# One_Dimensional_Pong_-_Rev_A_1.net
KiCad netlist of a schematic drawn in EAGLE
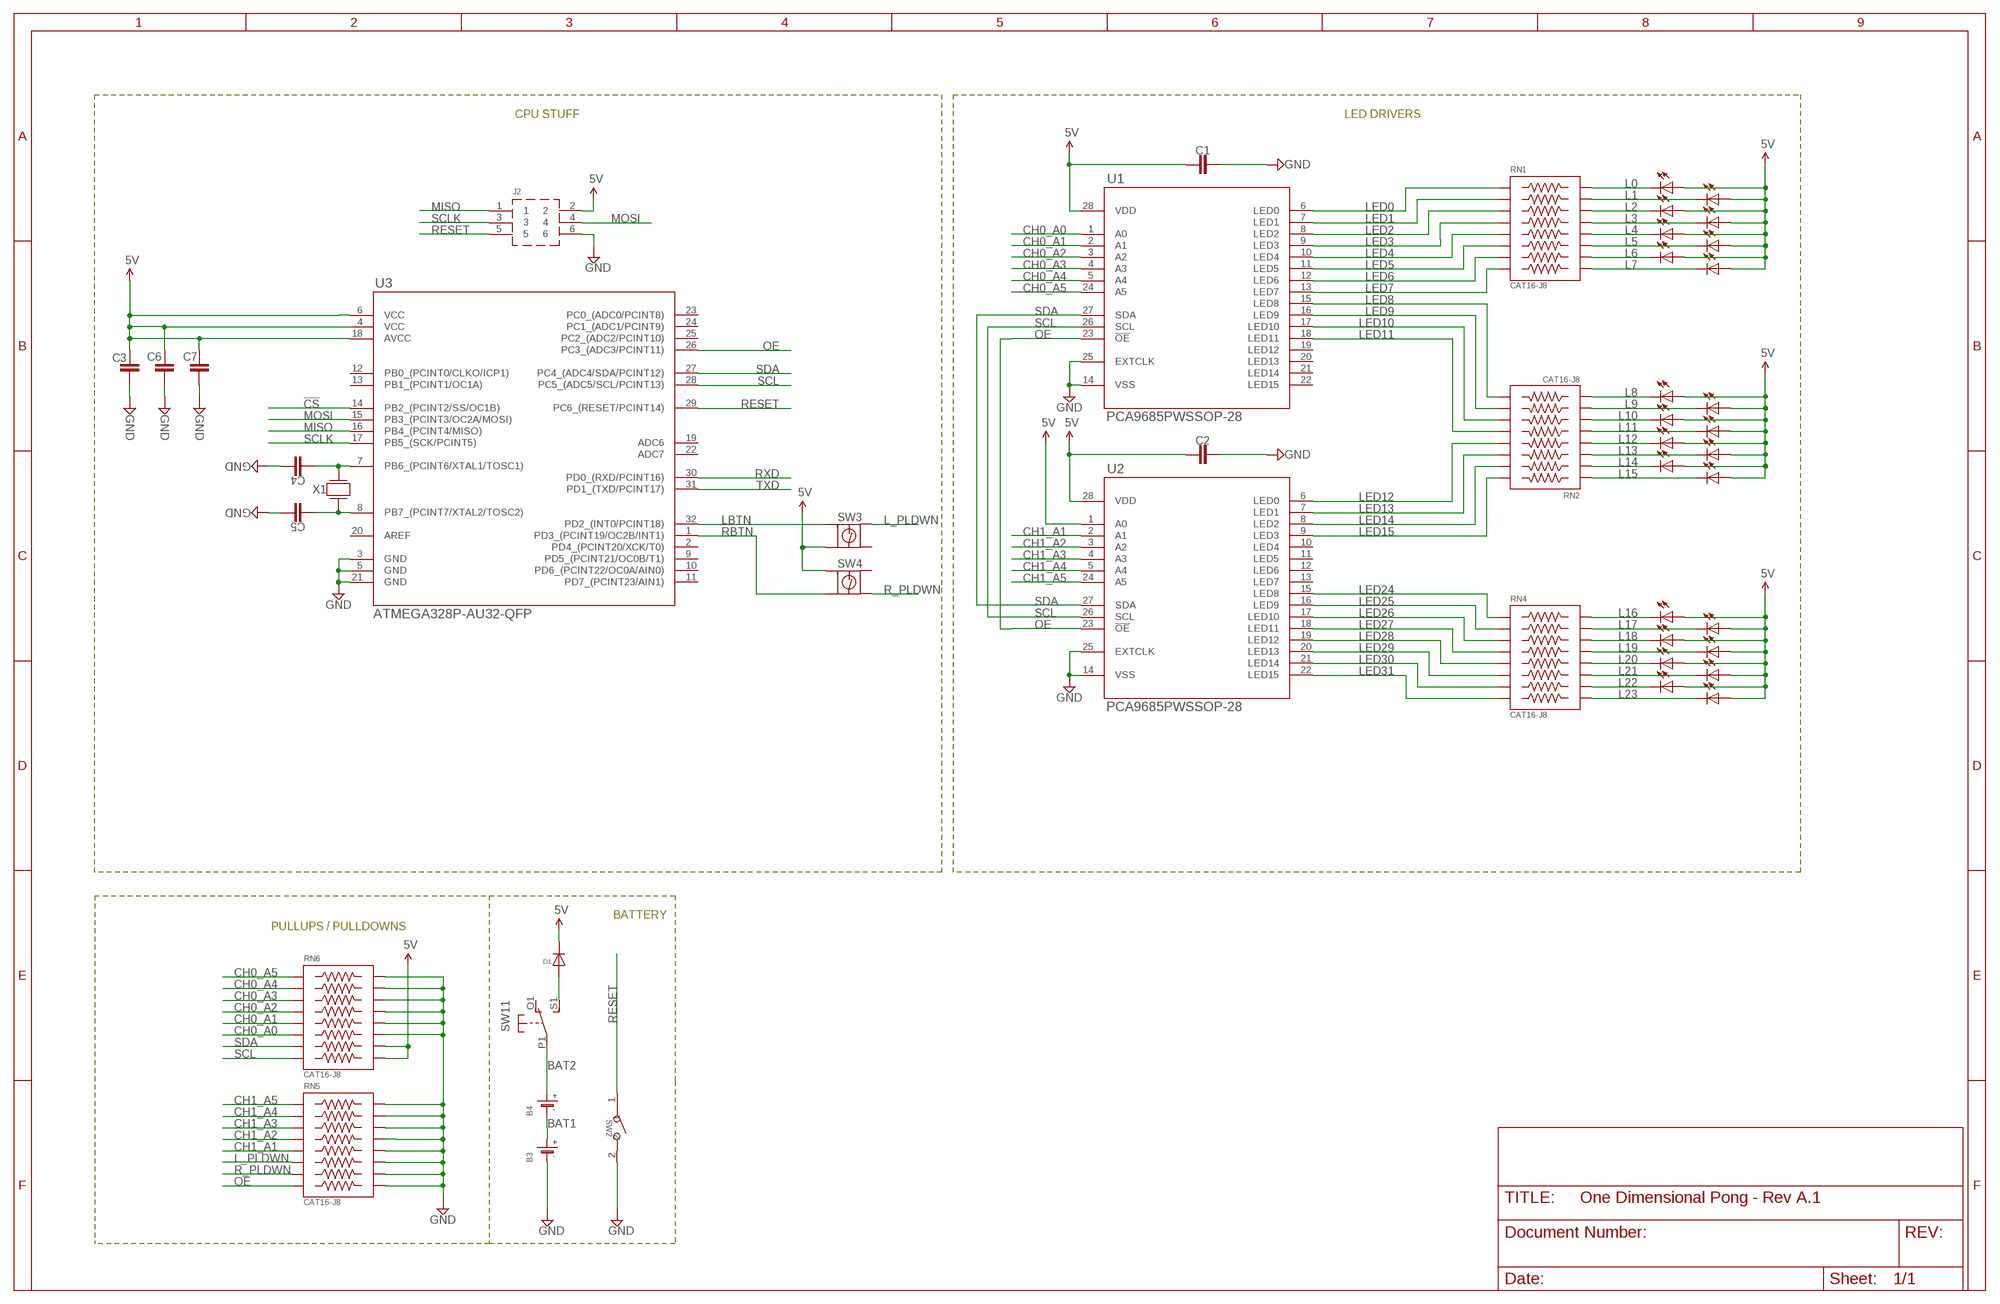
[diagram p0: schematic, sheet 1]

(export (version "E")
  (design (tool "Eeschema 10.0.6"))
  (components
    (comp (ref "B3")
      (value "BATTERYCR2540-SMT")
      (footprint "eagle-import:CR2450")
      (libsource (lib "eagle-import") (part "BATTERYCR2540-SMT"))
    )
    (comp (ref "B4")
      (value "BATTERYCR2540-SMT")
      (footprint "eagle-import:CR2450")
      (libsource (lib "eagle-import") (part "BATTERYCR2540-SMT"))
    )
    (comp (ref "C1")
      (value "C-EUC0805")
      (footprint "eagle-import:C0805")
      (libsource (lib "eagle-import") (part "C-EUC0805"))
    )
    (comp (ref "C2")
      (value "C-EUC0805")
      (footprint "eagle-import:C0805")
      (libsource (lib "eagle-import") (part "C-EUC0805"))
    )
    (comp (ref "C3")
      (value "C-EUC0805")
      (footprint "eagle-import:C0805")
      (libsource (lib "eagle-import") (part "C-EUC0805"))
    )
    (comp (ref "C4")
      (value "C-EUC0805")
      (footprint "eagle-import:C0805")
      (libsource (lib "eagle-import") (part "C-EUC0805"))
    )
    (comp (ref "C5")
      (value "C-EUC0805")
      (footprint "eagle-import:C0805")
      (libsource (lib "eagle-import") (part "C-EUC0805"))
    )
    (comp (ref "C6")
      (value "C-EUC0805")
      (footprint "eagle-import:C0805")
      (libsource (lib "eagle-import") (part "C-EUC0805"))
    )
    (comp (ref "C7")
      (value "C-EUC0805")
      (footprint "eagle-import:C0805")
      (libsource (lib "eagle-import") (part "C-EUC0805"))
    )
    (comp (ref "D1")
      (value "1N4150W")
      (footprint "eagle-import:SOD-123")
      (libsource (lib "eagle-import") (part "1N4150W"))
    )
    (comp (ref "J2")
      (value "610106249121")
      (footprint "eagle-import:RA-SMT-HDR-2X3")
      (libsource (lib "eagle-import") (part "610106249121"))
    )
    (comp (ref "LED1")
      (value "LED0805-YELLOW")
      (footprint "eagle-import:CHIP-LED0805-YELLOW")
      (libsource (lib "eagle-import") (part "LED0805-YELLOW"))
    )
    (comp (ref "LED2")
      (value "LED0805-ORANGE")
      (footprint "eagle-import:CHIP-LED0805-ORANGE")
      (libsource (lib "eagle-import") (part "LED0805-ORANGE"))
    )
    (comp (ref "LED3")
      (value "LEDCHIPLED_0805")
      (footprint "eagle-import:CHIPLED_0805")
      (libsource (lib "eagle-import") (part "LEDCHIPLED_0805"))
    )
    (comp (ref "LED4")
      (value "LED0805-ORANGE")
      (footprint "eagle-import:CHIP-LED0805-ORANGE")
      (libsource (lib "eagle-import") (part "LED0805-ORANGE"))
    )
    (comp (ref "LED5")
      (value "LED0805-YELLOW")
      (footprint "eagle-import:CHIP-LED0805-YELLOW")
      (libsource (lib "eagle-import") (part "LED0805-YELLOW"))
    )
    (comp (ref "LED6")
      (value "LED0805-GREEN")
      (footprint "eagle-import:CHIP-LED0805-GREEN")
      (libsource (lib "eagle-import") (part "LED0805-GREEN"))
    )
    (comp (ref "LED7")
      (value "LED0805-GREEN")
      (footprint "eagle-import:CHIP-LED0805-GREEN")
      (libsource (lib "eagle-import") (part "LED0805-GREEN"))
    )
    (comp (ref "LED8")
      (value "LED0805-GREEN")
      (footprint "eagle-import:CHIP-LED0805-GREEN")
      (libsource (lib "eagle-import") (part "LED0805-GREEN"))
    )
    (comp (ref "LED9")
      (value "LED0805-GREEN")
      (footprint "eagle-import:CHIP-LED0805-GREEN")
      (libsource (lib "eagle-import") (part "LED0805-GREEN"))
    )
    (comp (ref "LED10")
      (value "LED0805-GREEN")
      (footprint "eagle-import:CHIP-LED0805-GREEN")
      (libsource (lib "eagle-import") (part "LED0805-GREEN"))
    )
    (comp (ref "LED11")
      (value "LED0805-GREEN")
      (footprint "eagle-import:CHIP-LED0805-GREEN")
      (libsource (lib "eagle-import") (part "LED0805-GREEN"))
    )
    (comp (ref "LED12")
      (value "LED0805-GREEN")
      (footprint "eagle-import:CHIP-LED0805-GREEN")
      (libsource (lib "eagle-import") (part "LED0805-GREEN"))
    )
    (comp (ref "LED13")
      (value "LED0805-GREEN")
      (footprint "eagle-import:CHIP-LED0805-GREEN")
      (libsource (lib "eagle-import") (part "LED0805-GREEN"))
    )
    (comp (ref "LED14")
      (value "LED0805-GREEN")
      (footprint "eagle-import:CHIP-LED0805-GREEN")
      (libsource (lib "eagle-import") (part "LED0805-GREEN"))
    )
    (comp (ref "LED15")
      (value "LED0805-GREEN")
      (footprint "eagle-import:CHIP-LED0805-GREEN")
      (libsource (lib "eagle-import") (part "LED0805-GREEN"))
    )
    (comp (ref "LED16")
      (value "LED0805-GREEN")
      (footprint "eagle-import:CHIP-LED0805-GREEN")
      (libsource (lib "eagle-import") (part "LED0805-GREEN"))
    )
    (comp (ref "LED25")
      (value "LED0805-GREEN")
      (footprint "eagle-import:CHIP-LED0805-GREEN")
      (libsource (lib "eagle-import") (part "LED0805-GREEN"))
    )
    (comp (ref "LED26")
      (value "LED0805-GREEN")
      (footprint "eagle-import:CHIP-LED0805-GREEN")
      (libsource (lib "eagle-import") (part "LED0805-GREEN"))
    )
    (comp (ref "LED27")
      (value "LED0805-GREEN")
      (footprint "eagle-import:CHIP-LED0805-GREEN")
      (libsource (lib "eagle-import") (part "LED0805-GREEN"))
    )
    (comp (ref "LED28")
      (value "LED0805-YELLOW")
      (footprint "eagle-import:CHIP-LED0805-YELLOW")
      (libsource (lib "eagle-import") (part "LED0805-YELLOW"))
    )
    (comp (ref "LED29")
      (value "LED0805-ORANGE")
      (footprint "eagle-import:CHIP-LED0805-ORANGE")
      (libsource (lib "eagle-import") (part "LED0805-ORANGE"))
    )
    (comp (ref "LED30")
      (value "LEDCHIPLED_0805")
      (footprint "eagle-import:CHIPLED_0805")
      (libsource (lib "eagle-import") (part "LEDCHIPLED_0805"))
    )
    (comp (ref "LED31")
      (value "LED0805-ORANGE")
      (footprint "eagle-import:CHIP-LED0805-ORANGE")
      (libsource (lib "eagle-import") (part "LED0805-ORANGE"))
    )
    (comp (ref "LED32")
      (value "LED0805-YELLOW")
      (footprint "eagle-import:CHIP-LED0805-YELLOW")
      (libsource (lib "eagle-import") (part "LED0805-YELLOW"))
    )
    (comp (ref "RN1")
      (value "CAT16-J8")
      (footprint "eagle-import:RN8")
      (libsource (lib "eagle-import") (part "CAT16-J8"))
    )
    (comp (ref "RN2")
      (value "CAT16-J8")
      (footprint "eagle-import:RN8")
      (libsource (lib "eagle-import") (part "CAT16-J8"))
    )
    (comp (ref "RN4")
      (value "CAT16-J8")
      (footprint "eagle-import:RN8")
      (libsource (lib "eagle-import") (part "CAT16-J8"))
    )
    (comp (ref "RN5")
      (value "CAT16-J8")
      (footprint "eagle-import:RN8")
      (libsource (lib "eagle-import") (part "CAT16-J8"))
    )
    (comp (ref "RN6")
      (value "CAT16-J8")
      (footprint "eagle-import:RN8")
      (libsource (lib "eagle-import") (part "CAT16-J8"))
    )
    (comp (ref "SW1")
      (value "DPDT-EG1390")
      (footprint "eagle-import:EG1390")
      (libsource (lib "eagle-import") (part "DPDT-EG1390"))
    )
    (comp (ref "SW2")
      (value "B3U-1000P-2P-SMD")
      (footprint "eagle-import:SW2-2.6-3.0X2.5X1.2+0.4MM")
      (fields (field (name "SPICEPREFIX") "B"))
      (libsource (lib "eagle-import") (part "SMD-BUTTON(2P-3.0X2.5X1.2+0.4MM)-B3U-1000P-2P-SMD"))
    )
    (comp (ref "SW3")
      (value "PTS645SM43SMTR92LFS")
      (footprint "eagle-import:PTS645-SMT-6MM")
      (libsource (lib "eagle-import") (part "PTS645SM43SMTR92LFS"))
    )
    (comp (ref "SW4")
      (value "PTS645SM43SMTR92LFS")
      (footprint "eagle-import:PTS645-SMT-6MM")
      (libsource (lib "eagle-import") (part "PTS645SM43SMTR92LFS"))
    )
    (comp (ref "U1")
      (value "PCA9685PWSSOP-28")
      (footprint "eagle-import:SOP65P640X110-28")
      (libsource (lib "eagle-import") (part "PCA9685PWSSOP-28"))
    )
    (comp (ref "U2")
      (value "PCA9685PWSSOP-28")
      (footprint "eagle-import:SOP65P640X110-28")
      (libsource (lib "eagle-import") (part "PCA9685PWSSOP-28"))
    )
    (comp (ref "U3")
      (value "ATMEGA328P-AU32-QFP")
      (footprint "eagle-import:QFP80P897X897X120-32")
      (libsource (lib "eagle-import") (part "ATMEGA328P-AU32-QFP"))
    )
    (comp (ref "X1")
      (value "ABLS-16.000MHZ-B4-T")
      (footprint "eagle-import:OSC12P7X4P7")
      (libsource (lib "eagle-import") (part "ABLS-16.000MHZ-B4-T"))
    )
  )
  (nets
    (net (code "1") (name "/BAT1") (class "Default")
      (node (ref "B3") (pin "1") (pinfunction "+_1") (pintype "passive"))
      (node (ref "B3") (pin "2") (pinfunction "+_2") (pintype "passive"))
      (node (ref "B4") (pin "GND") (pinfunction "-_GND") (pintype "passive"))
    )
    (net (code "2") (name "/BAT2") (class "Default")
      (node (ref "B4") (pin "1") (pinfunction "+_1") (pintype "passive"))
      (node (ref "B4") (pin "2") (pinfunction "+_2") (pintype "passive"))
      (node (ref "SW1") (pin "P1") (pinfunction "P_P1") (pintype "passive"))
    )
    (net (code "3") (name "/CH0_A0") (class "Default")
      (node (ref "RN6") (pin "11") (pinfunction "11_11") (pintype "passive"))
      (node (ref "U1") (pin "1") (pinfunction "A0_1") (pintype "passive"))
    )
    (net (code "4") (name "/CH0_A1") (class "Default")
      (node (ref "RN6") (pin "9") (pinfunction "9_9") (pintype "passive"))
      (node (ref "U1") (pin "2") (pinfunction "A1_2") (pintype "passive"))
    )
    (net (code "5") (name "/CH0_A2") (class "Default")
      (node (ref "RN6") (pin "7") (pinfunction "7_7") (pintype "passive"))
      (node (ref "U1") (pin "3") (pinfunction "A2_3") (pintype "passive"))
    )
    (net (code "6") (name "/CH0_A3") (class "Default")
      (node (ref "RN6") (pin "5") (pinfunction "5_5") (pintype "passive"))
      (node (ref "U1") (pin "4") (pinfunction "A3_4") (pintype "passive"))
    )
    (net (code "7") (name "/CH0_A4") (class "Default")
      (node (ref "RN6") (pin "3") (pinfunction "3_3") (pintype "passive"))
      (node (ref "U1") (pin "5") (pinfunction "A4_5") (pintype "passive"))
    )
    (net (code "8") (name "/CH0_A5") (class "Default")
      (node (ref "RN6") (pin "1") (pinfunction "1_1") (pintype "passive"))
      (node (ref "U1") (pin "24") (pinfunction "A5_24") (pintype "passive"))
    )
    (net (code "9") (name "/CH1_A1") (class "Default")
      (node (ref "RN5") (pin "9") (pinfunction "9_9") (pintype "passive"))
      (node (ref "U2") (pin "2") (pinfunction "A1_2") (pintype "passive"))
    )
    (net (code "10") (name "/CH1_A2") (class "Default")
      (node (ref "RN5") (pin "7") (pinfunction "7_7") (pintype "passive"))
      (node (ref "U2") (pin "3") (pinfunction "A2_3") (pintype "passive"))
    )
    (net (code "11") (name "/CH1_A3") (class "Default")
      (node (ref "RN5") (pin "5") (pinfunction "5_5") (pintype "passive"))
      (node (ref "U2") (pin "4") (pinfunction "A3_4") (pintype "passive"))
    )
    (net (code "12") (name "/CH1_A4") (class "Default")
      (node (ref "RN5") (pin "3") (pinfunction "3_3") (pintype "passive"))
      (node (ref "U2") (pin "5") (pinfunction "A4_5") (pintype "passive"))
    )
    (net (code "13") (name "/CH1_A5") (class "Default")
      (node (ref "RN5") (pin "1") (pinfunction "1_1") (pintype "passive"))
      (node (ref "U2") (pin "24") (pinfunction "A5_24") (pintype "passive"))
    )
    (net (code "14") (name "/L0") (class "Default")
      (node (ref "LED1") (pin "C") (pinfunction "C_C") (pintype "passive"))
      (node (ref "RN1") (pin "2") (pinfunction "2_2") (pintype "passive"))
    )
    (net (code "15") (name "/L1") (class "Default")
      (node (ref "LED2") (pin "C") (pinfunction "C_C") (pintype "passive"))
      (node (ref "RN1") (pin "4") (pinfunction "4_4") (pintype "passive"))
    )
    (net (code "16") (name "/L2") (class "Default")
      (node (ref "LED3") (pin "C") (pinfunction "C_C") (pintype "passive"))
      (node (ref "RN1") (pin "6") (pinfunction "6_6") (pintype "passive"))
    )
    (net (code "17") (name "/L3") (class "Default")
      (node (ref "LED4") (pin "C") (pinfunction "C_C") (pintype "passive"))
      (node (ref "RN1") (pin "8") (pinfunction "8_8") (pintype "passive"))
    )
    (net (code "18") (name "/L4") (class "Default")
      (node (ref "LED5") (pin "C") (pinfunction "C_C") (pintype "passive"))
      (node (ref "RN1") (pin "10") (pinfunction "10_10") (pintype "passive"))
    )
    (net (code "19") (name "/L5") (class "Default")
      (node (ref "LED6") (pin "C") (pinfunction "C_C") (pintype "passive"))
      (node (ref "RN1") (pin "12") (pinfunction "12_12") (pintype "passive"))
    )
    (net (code "20") (name "/L6") (class "Default")
      (node (ref "LED7") (pin "C") (pinfunction "C_C") (pintype "passive"))
      (node (ref "RN1") (pin "14") (pinfunction "14_14") (pintype "passive"))
    )
    (net (code "21") (name "/L7") (class "Default")
      (node (ref "LED8") (pin "C") (pinfunction "C_C") (pintype "passive"))
      (node (ref "RN1") (pin "16") (pinfunction "16_16") (pintype "passive"))
    )
    (net (code "22") (name "/L8") (class "Default")
      (node (ref "LED9") (pin "C") (pinfunction "C_C") (pintype "passive"))
      (node (ref "RN2") (pin "15") (pinfunction "15_15") (pintype "passive"))
    )
    (net (code "23") (name "/L9") (class "Default")
      (node (ref "LED10") (pin "C") (pinfunction "C_C") (pintype "passive"))
      (node (ref "RN2") (pin "13") (pinfunction "13_13") (pintype "passive"))
    )
    (net (code "24") (name "/L10") (class "Default")
      (node (ref "LED11") (pin "C") (pinfunction "C_C") (pintype "passive"))
      (node (ref "RN2") (pin "11") (pinfunction "11_11") (pintype "passive"))
    )
    (net (code "25") (name "/L11") (class "Default")
      (node (ref "LED12") (pin "C") (pinfunction "C_C") (pintype "passive"))
      (node (ref "RN2") (pin "9") (pinfunction "9_9") (pintype "passive"))
    )
    (net (code "26") (name "/L12") (class "Default")
      (node (ref "LED13") (pin "C") (pinfunction "C_C") (pintype "passive"))
      (node (ref "RN2") (pin "7") (pinfunction "7_7") (pintype "passive"))
    )
    (net (code "27") (name "/L13") (class "Default")
      (node (ref "LED14") (pin "C") (pinfunction "C_C") (pintype "passive"))
      (node (ref "RN2") (pin "5") (pinfunction "5_5") (pintype "passive"))
    )
    (net (code "28") (name "/L14") (class "Default")
      (node (ref "LED15") (pin "C") (pinfunction "C_C") (pintype "passive"))
      (node (ref "RN2") (pin "3") (pinfunction "3_3") (pintype "passive"))
    )
    (net (code "29") (name "/L15") (class "Default")
      (node (ref "LED16") (pin "C") (pinfunction "C_C") (pintype "passive"))
      (node (ref "RN2") (pin "1") (pinfunction "1_1") (pintype "passive"))
    )
    (net (code "30") (name "/L16") (class "Default")
      (node (ref "LED25") (pin "C") (pinfunction "C_C") (pintype "passive"))
      (node (ref "RN4") (pin "2") (pinfunction "2_2") (pintype "passive"))
    )
    (net (code "31") (name "/L17") (class "Default")
      (node (ref "LED26") (pin "C") (pinfunction "C_C") (pintype "passive"))
      (node (ref "RN4") (pin "4") (pinfunction "4_4") (pintype "passive"))
    )
    (net (code "32") (name "/L18") (class "Default")
      (node (ref "LED27") (pin "C") (pinfunction "C_C") (pintype "passive"))
      (node (ref "RN4") (pin "6") (pinfunction "6_6") (pintype "passive"))
    )
    (net (code "33") (name "/L19") (class "Default")
      (node (ref "LED28") (pin "C") (pinfunction "C_C") (pintype "passive"))
      (node (ref "RN4") (pin "8") (pinfunction "8_8") (pintype "passive"))
    )
    (net (code "34") (name "/L20") (class "Default")
      (node (ref "LED29") (pin "C") (pinfunction "C_C") (pintype "passive"))
      (node (ref "RN4") (pin "10") (pinfunction "10_10") (pintype "passive"))
    )
    (net (code "35") (name "/L21") (class "Default")
      (node (ref "LED30") (pin "C") (pinfunction "C_C") (pintype "passive"))
      (node (ref "RN4") (pin "12") (pinfunction "12_12") (pintype "passive"))
    )
    (net (code "36") (name "/L22") (class "Default")
      (node (ref "LED31") (pin "C") (pinfunction "C_C") (pintype "passive"))
      (node (ref "RN4") (pin "14") (pinfunction "14_14") (pintype "passive"))
    )
    (net (code "37") (name "/L23") (class "Default")
      (node (ref "LED32") (pin "C") (pinfunction "C_C") (pintype "passive"))
      (node (ref "RN4") (pin "16") (pinfunction "16_16") (pintype "passive"))
    )
    (net (code "38") (name "/LBTN") (class "Default")
      (node (ref "SW3") (pin "P$1") (pinfunction "1_P$1") (pintype "bidirectional"))
      (node (ref "U3") (pin "32") (pinfunction "PD2_(INT0/PCINT18)_32") (pintype "bidirectional"))
    )
    (net (code "39") (name "/LED0") (class "Default")
      (node (ref "RN1") (pin "1") (pinfunction "1_1") (pintype "passive"))
      (node (ref "U1") (pin "6") (pinfunction "LED0_6") (pintype "passive"))
    )
    (net (code "40") (name "/LED1") (class "Default")
      (node (ref "RN1") (pin "3") (pinfunction "3_3") (pintype "passive"))
      (node (ref "U1") (pin "7") (pinfunction "LED1_7") (pintype "passive"))
    )
    (net (code "41") (name "/LED2") (class "Default")
      (node (ref "RN1") (pin "5") (pinfunction "5_5") (pintype "passive"))
      (node (ref "U1") (pin "8") (pinfunction "LED2_8") (pintype "passive"))
    )
    (net (code "42") (name "/LED3") (class "Default")
      (node (ref "RN1") (pin "7") (pinfunction "7_7") (pintype "passive"))
      (node (ref "U1") (pin "9") (pinfunction "LED3_9") (pintype "passive"))
    )
    (net (code "43") (name "/LED4") (class "Default")
      (node (ref "RN1") (pin "9") (pinfunction "9_9") (pintype "passive"))
      (node (ref "U1") (pin "10") (pinfunction "LED4_10") (pintype "passive"))
    )
    (net (code "44") (name "/LED5") (class "Default")
      (node (ref "RN1") (pin "11") (pinfunction "11_11") (pintype "passive"))
      (node (ref "U1") (pin "11") (pinfunction "LED5_11") (pintype "passive"))
    )
    (net (code "45") (name "/LED6") (class "Default")
      (node (ref "RN1") (pin "13") (pinfunction "13_13") (pintype "passive"))
      (node (ref "U1") (pin "12") (pinfunction "LED6_12") (pintype "passive"))
    )
    (net (code "46") (name "/LED7") (class "Default")
      (node (ref "RN1") (pin "15") (pinfunction "15_15") (pintype "passive"))
      (node (ref "U1") (pin "13") (pinfunction "LED7_13") (pintype "passive"))
    )
    (net (code "47") (name "/LED8") (class "Default")
      (node (ref "RN2") (pin "16") (pinfunction "16_16") (pintype "passive"))
      (node (ref "U1") (pin "15") (pinfunction "LED8_15") (pintype "passive"))
    )
    (net (code "48") (name "/LED9") (class "Default")
      (node (ref "RN2") (pin "14") (pinfunction "14_14") (pintype "passive"))
      (node (ref "U1") (pin "16") (pinfunction "LED9_16") (pintype "passive"))
    )
    (net (code "49") (name "/LED10") (class "Default")
      (node (ref "RN2") (pin "12") (pinfunction "12_12") (pintype "passive"))
      (node (ref "U1") (pin "17") (pinfunction "LED10_17") (pintype "passive"))
    )
    (net (code "50") (name "/LED11") (class "Default")
      (node (ref "RN2") (pin "10") (pinfunction "10_10") (pintype "passive"))
      (node (ref "U1") (pin "18") (pinfunction "LED11_18") (pintype "passive"))
    )
    (net (code "51") (name "/LED12") (class "Default")
      (node (ref "RN2") (pin "8") (pinfunction "8_8") (pintype "passive"))
      (node (ref "U2") (pin "6") (pinfunction "LED0_6") (pintype "passive"))
    )
    (net (code "52") (name "/LED13") (class "Default")
      (node (ref "RN2") (pin "6") (pinfunction "6_6") (pintype "passive"))
      (node (ref "U2") (pin "7") (pinfunction "LED1_7") (pintype "passive"))
    )
    (net (code "53") (name "/LED14") (class "Default")
      (node (ref "RN2") (pin "4") (pinfunction "4_4") (pintype "passive"))
      (node (ref "U2") (pin "8") (pinfunction "LED2_8") (pintype "passive"))
    )
    (net (code "54") (name "/LED15") (class "Default")
      (node (ref "RN2") (pin "2") (pinfunction "2_2") (pintype "passive"))
      (node (ref "U2") (pin "9") (pinfunction "LED3_9") (pintype "passive"))
    )
    (net (code "55") (name "/LED24") (class "Default")
      (node (ref "RN4") (pin "1") (pinfunction "1_1") (pintype "passive"))
      (node (ref "U2") (pin "15") (pinfunction "LED8_15") (pintype "passive"))
    )
    (net (code "56") (name "/LED25") (class "Default")
      (node (ref "RN4") (pin "3") (pinfunction "3_3") (pintype "passive"))
      (node (ref "U2") (pin "16") (pinfunction "LED9_16") (pintype "passive"))
    )
    (net (code "57") (name "/LED26") (class "Default")
      (node (ref "RN4") (pin "5") (pinfunction "5_5") (pintype "passive"))
      (node (ref "U2") (pin "17") (pinfunction "LED10_17") (pintype "passive"))
    )
    (net (code "58") (name "/LED27") (class "Default")
      (node (ref "RN4") (pin "7") (pinfunction "7_7") (pintype "passive"))
      (node (ref "U2") (pin "18") (pinfunction "LED11_18") (pintype "passive"))
    )
    (net (code "59") (name "/LED28") (class "Default")
      (node (ref "RN4") (pin "9") (pinfunction "9_9") (pintype "passive"))
      (node (ref "U2") (pin "19") (pinfunction "LED12_19") (pintype "passive"))
    )
    (net (code "60") (name "/LED29") (class "Default")
      (node (ref "RN4") (pin "11") (pinfunction "11_11") (pintype "passive"))
      (node (ref "U2") (pin "20") (pinfunction "LED13_20") (pintype "passive"))
    )
    (net (code "61") (name "/LED30") (class "Default")
      (node (ref "RN4") (pin "13") (pinfunction "13_13") (pintype "passive"))
      (node (ref "U2") (pin "21") (pinfunction "LED14_21") (pintype "passive"))
    )
    (net (code "62") (name "/LED31") (class "Default")
      (node (ref "RN4") (pin "15") (pinfunction "15_15") (pintype "passive"))
      (node (ref "U2") (pin "22") (pinfunction "LED15_22") (pintype "passive"))
    )
    (net (code "63") (name "/L_PLDWN") (class "Default")
      (node (ref "RN5") (pin "11") (pinfunction "11_11") (pintype "passive"))
      (node (ref "SW3") (pin "P$2") (pinfunction "2_P$2") (pintype "bidirectional"))
    )
    (net (code "64") (name "/MISO") (class "Default")
      (node (ref "J2") (pin "1") (pinfunction "1_1") (pintype "bidirectional"))
      (node (ref "U3") (pin "16") (pinfunction "PB4_(PCINT4/MISO)_16") (pintype "bidirectional"))
    )
    (net (code "65") (name "/MOSI") (class "Default")
      (node (ref "J2") (pin "4") (pinfunction "4_4") (pintype "bidirectional"))
      (node (ref "U3") (pin "15") (pinfunction "PB3_(PCINT3/OC2A/MOSI)_15") (pintype "bidirectional"))
    )
    (net (code "66") (name "/OE") (class "Default")
      (node (ref "RN5") (pin "15") (pinfunction "15_15") (pintype "passive"))
      (node (ref "U1") (pin "23") (pinfunction "~{OE}_23") (pintype "passive"))
      (node (ref "U2") (pin "23") (pinfunction "~{OE}_23") (pintype "passive"))
      (node (ref "U3") (pin "26") (pinfunction "PC3_(ADC3/PCINT11)_26") (pintype "bidirectional"))
    )
    (net (code "67") (name "/RBTN") (class "Default")
      (node (ref "SW4") (pin "P$3") (pinfunction "3_P$3") (pintype "bidirectional"))
      (node (ref "U3") (pin "1") (pinfunction "PD3_(PCINT19/OC2B/INT1)_1") (pintype "bidirectional"))
    )
    (net (code "68") (name "/RESET") (class "Default")
      (node (ref "J2") (pin "5") (pinfunction "5_5") (pintype "bidirectional"))
      (node (ref "SW2") (pin "1") (pinfunction "1_1") (pintype "bidirectional"))
      (node (ref "U3") (pin "29") (pinfunction "PC6_(RESET/PCINT14)_29") (pintype "bidirectional"))
    )
    (net (code "69") (name "/RXD") (class "Default")
      (node (ref "U3") (pin "30") (pinfunction "PD0_(RXD/PCINT16)_30") (pintype "bidirectional"))
    )
    (net (code "70") (name "/R_PLDWN") (class "Default")
      (node (ref "RN5") (pin "13") (pinfunction "13_13") (pintype "passive"))
      (node (ref "SW4") (pin "P$4") (pinfunction "4_P$4") (pintype "bidirectional"))
    )
    (net (code "71") (name "/SCL") (class "Default")
      (node (ref "RN6") (pin "15") (pinfunction "15_15") (pintype "passive"))
      (node (ref "U1") (pin "26") (pinfunction "SCL_26") (pintype "passive"))
      (node (ref "U2") (pin "26") (pinfunction "SCL_26") (pintype "passive"))
      (node (ref "U3") (pin "28") (pinfunction "PC5_(ADC5/SCL/PCINT13)_28") (pintype "bidirectional"))
    )
    (net (code "72") (name "/SCLK") (class "Default")
      (node (ref "J2") (pin "3") (pinfunction "3_3") (pintype "bidirectional"))
      (node (ref "U3") (pin "17") (pinfunction "PB5_(SCK/PCINT5)_17") (pintype "bidirectional"))
    )
    (net (code "73") (name "/SDA") (class "Default")
      (node (ref "RN6") (pin "13") (pinfunction "13_13") (pintype "passive"))
      (node (ref "U1") (pin "27") (pinfunction "SDA_27") (pintype "passive"))
      (node (ref "U2") (pin "27") (pinfunction "SDA_27") (pintype "passive"))
      (node (ref "U3") (pin "27") (pinfunction "PC4_(ADC4/SDA/PCINT12)_27") (pintype "bidirectional"))
    )
    (net (code "74") (name "/TXD") (class "Default")
      (node (ref "U3") (pin "31") (pinfunction "PD1_(TXD/PCINT17)_31") (pintype "bidirectional"))
    )
    (net (code "75") (name "/~{CS}") (class "Default")
      (node (ref "U3") (pin "14") (pinfunction "PB2_(PCINT2/SS/OC1B)_14") (pintype "bidirectional"))
    )
    (net (code "76") (name "5V") (class "Default")
      (node (ref "C1") (pin "1") (pinfunction "1_1") (pintype "passive"))
      (node (ref "C2") (pin "1") (pinfunction "1_1") (pintype "passive"))
      (node (ref "C3") (pin "1") (pinfunction "1_1") (pintype "passive"))
      (node (ref "C6") (pin "1") (pinfunction "1_1") (pintype "passive"))
      (node (ref "C7") (pin "1") (pinfunction "1_1") (pintype "passive"))
      (node (ref "D1") (pin "K") (pinfunction "C_K") (pintype "passive"))
      (node (ref "J2") (pin "2") (pinfunction "2_2") (pintype "bidirectional"))
      (node (ref "LED1") (pin "A") (pinfunction "A_A") (pintype "passive"))
      (node (ref "LED10") (pin "A") (pinfunction "A_A") (pintype "passive"))
      (node (ref "LED11") (pin "A") (pinfunction "A_A") (pintype "passive"))
      (node (ref "LED12") (pin "A") (pinfunction "A_A") (pintype "passive"))
      (node (ref "LED13") (pin "A") (pinfunction "A_A") (pintype "passive"))
      (node (ref "LED14") (pin "A") (pinfunction "A_A") (pintype "passive"))
      (node (ref "LED15") (pin "A") (pinfunction "A_A") (pintype "passive"))
      (node (ref "LED16") (pin "A") (pinfunction "A_A") (pintype "passive"))
      (node (ref "LED2") (pin "A") (pinfunction "A_A") (pintype "passive"))
      (node (ref "LED25") (pin "A") (pinfunction "A_A") (pintype "passive"))
      (node (ref "LED26") (pin "A") (pinfunction "A_A") (pintype "passive"))
      (node (ref "LED27") (pin "A") (pinfunction "A_A") (pintype "passive"))
      (node (ref "LED28") (pin "A") (pinfunction "A_A") (pintype "passive"))
      (node (ref "LED29") (pin "A") (pinfunction "A_A") (pintype "passive"))
      (node (ref "LED3") (pin "A") (pinfunction "A_A") (pintype "passive"))
      (node (ref "LED30") (pin "A") (pinfunction "A_A") (pintype "passive"))
      (node (ref "LED31") (pin "A") (pinfunction "A_A") (pintype "passive"))
      (node (ref "LED32") (pin "A") (pinfunction "A_A") (pintype "passive"))
      (node (ref "LED4") (pin "A") (pinfunction "A_A") (pintype "passive"))
      (node (ref "LED5") (pin "A") (pinfunction "A_A") (pintype "passive"))
      (node (ref "LED6") (pin "A") (pinfunction "A_A") (pintype "passive"))
      (node (ref "LED7") (pin "A") (pinfunction "A_A") (pintype "passive"))
      (node (ref "LED8") (pin "A") (pinfunction "A_A") (pintype "passive"))
      (node (ref "LED9") (pin "A") (pinfunction "A_A") (pintype "passive"))
      (node (ref "RN6") (pin "14") (pinfunction "14_14") (pintype "passive"))
      (node (ref "RN6") (pin "16") (pinfunction "16_16") (pintype "passive"))
      (node (ref "SW3") (pin "P$3") (pinfunction "3_P$3") (pintype "bidirectional"))
      (node (ref "SW4") (pin "P$1") (pinfunction "1_P$1") (pintype "bidirectional"))
      (node (ref "U1") (pin "28") (pinfunction "VDD_28") (pintype "passive"))
      (node (ref "U2") (pin "1") (pinfunction "A0_1") (pintype "passive"))
      (node (ref "U2") (pin "28") (pinfunction "VDD_28") (pintype "passive"))
      (node (ref "U3") (pin "18") (pinfunction "AVCC_18") (pintype "power_in"))
      (node (ref "U3") (pin "4") (pinfunction "VCC_4") (pintype "power_in"))
      (node (ref "U3") (pin "6") (pinfunction "VCC_6") (pintype "power_in"))
    )
    (net (code "77") (name "GND") (class "Default")
      (node (ref "B3") (pin "GND") (pinfunction "-_GND") (pintype "passive"))
      (node (ref "C1") (pin "2") (pinfunction "2_2") (pintype "passive"))
      (node (ref "C2") (pin "2") (pinfunction "2_2") (pintype "passive"))
      (node (ref "C3") (pin "2") (pinfunction "2_2") (pintype "passive"))
      (node (ref "C4") (pin "2") (pinfunction "2_2") (pintype "passive"))
      (node (ref "C5") (pin "2") (pinfunction "2_2") (pintype "passive"))
      (node (ref "C6") (pin "2") (pinfunction "2_2") (pintype "passive"))
      (node (ref "C7") (pin "2") (pinfunction "2_2") (pintype "passive"))
      (node (ref "J2") (pin "6") (pinfunction "6_6") (pintype "bidirectional"))
      (node (ref "RN5") (pin "10") (pinfunction "10_10") (pintype "passive"))
      (node (ref "RN5") (pin "12") (pinfunction "12_12") (pintype "passive"))
      (node (ref "RN5") (pin "14") (pinfunction "14_14") (pintype "passive"))
      (node (ref "RN5") (pin "16") (pinfunction "16_16") (pintype "passive"))
      (node (ref "RN5") (pin "2") (pinfunction "2_2") (pintype "passive"))
      (node (ref "RN5") (pin "4") (pinfunction "4_4") (pintype "passive"))
      (node (ref "RN5") (pin "6") (pinfunction "6_6") (pintype "passive"))
      (node (ref "RN5") (pin "8") (pinfunction "8_8") (pintype "passive"))
      (node (ref "RN6") (pin "10") (pinfunction "10_10") (pintype "passive"))
      (node (ref "RN6") (pin "12") (pinfunction "12_12") (pintype "passive"))
      (node (ref "RN6") (pin "2") (pinfunction "2_2") (pintype "passive"))
      (node (ref "RN6") (pin "4") (pinfunction "4_4") (pintype "passive"))
      (node (ref "RN6") (pin "6") (pinfunction "6_6") (pintype "passive"))
      (node (ref "RN6") (pin "8") (pinfunction "8_8") (pintype "passive"))
      (node (ref "SW2") (pin "2") (pinfunction "2_2") (pintype "bidirectional"))
      (node (ref "U1") (pin "14") (pinfunction "VSS_14") (pintype "passive"))
      (node (ref "U1") (pin "25") (pinfunction "EXTCLK_25") (pintype "passive"))
      (node (ref "U2") (pin "14") (pinfunction "VSS_14") (pintype "passive"))
      (node (ref "U2") (pin "25") (pinfunction "EXTCLK_25") (pintype "passive"))
      (node (ref "U3") (pin "21") (pinfunction "GND_21") (pintype "power_in"))
      (node (ref "U3") (pin "3") (pinfunction "GND_3") (pintype "power_in"))
      (node (ref "U3") (pin "5") (pinfunction "GND_5") (pintype "power_in"))
    )
    (net (code "78") (name "Net-(SW1A-S)") (class "Default")
      (node (ref "D1") (pin "A") (pinfunction "A_A") (pintype "passive"))
      (node (ref "SW1") (pin "S1") (pinfunction "S_S1") (pintype "passive"))
    )
    (net (code "79") (name "Net-(U3-PB6_(PCINT6{slash}XTAL1{slash}TOSC1))") (class "Default")
      (node (ref "C4") (pin "1") (pinfunction "1_1") (pintype "passive"))
      (node (ref "U3") (pin "7") (pinfunction "PB6_(PCINT6/XTAL1/TOSC1)_7") (pintype "bidirectional"))
      (node (ref "X1") (pin "2") (pinfunction "2_2") (pintype "bidirectional"))
    )
    (net (code "80") (name "Net-(U3-PB7_(PCINT7{slash}XTAL2{slash}TOSC2))") (class "Default")
      (node (ref "C5") (pin "1") (pinfunction "1_1") (pintype "passive"))
      (node (ref "U3") (pin "8") (pinfunction "PB7_(PCINT7/XTAL2/TOSC2)_8") (pintype "bidirectional"))
      (node (ref "X1") (pin "1") (pinfunction "1_1") (pintype "bidirectional"))
    )
    (net (code "81") (name "unconnected-(SW1A-O-PadO1)") (class "Default")
      (node (ref "SW1") (pin "O1") (pinfunction "O_O1") (pintype "passive"))
    )
    (net (code "82") (name "unconnected-(SW3-4-PadP$4)") (class "Default")
      (node (ref "SW3") (pin "P$4") (pinfunction "4_P$4") (pintype "bidirectional"))
    )
    (net (code "83") (name "unconnected-(SW4-2-PadP$2)") (class "Default")
      (node (ref "SW4") (pin "P$2") (pinfunction "2_P$2") (pintype "bidirectional"))
    )
    (net (code "84") (name "unconnected-(U1-LED12-Pad19)") (class "Default")
      (node (ref "U1") (pin "19") (pinfunction "LED12_19") (pintype "passive"))
    )
    (net (code "85") (name "unconnected-(U1-LED13-Pad20)") (class "Default")
      (node (ref "U1") (pin "20") (pinfunction "LED13_20") (pintype "passive"))
    )
    (net (code "86") (name "unconnected-(U1-LED14-Pad21)") (class "Default")
      (node (ref "U1") (pin "21") (pinfunction "LED14_21") (pintype "passive"))
    )
    (net (code "87") (name "unconnected-(U1-LED15-Pad22)") (class "Default")
      (node (ref "U1") (pin "22") (pinfunction "LED15_22") (pintype "passive"))
    )
    (net (code "88") (name "unconnected-(U2-LED4-Pad10)") (class "Default")
      (node (ref "U2") (pin "10") (pinfunction "LED4_10") (pintype "passive"))
    )
    (net (code "89") (name "unconnected-(U2-LED5-Pad11)") (class "Default")
      (node (ref "U2") (pin "11") (pinfunction "LED5_11") (pintype "passive"))
    )
    (net (code "90") (name "unconnected-(U2-LED6-Pad12)") (class "Default")
      (node (ref "U2") (pin "12") (pinfunction "LED6_12") (pintype "passive"))
    )
    (net (code "91") (name "unconnected-(U2-LED7-Pad13)") (class "Default")
      (node (ref "U2") (pin "13") (pinfunction "LED7_13") (pintype "passive"))
    )
    (net (code "92") (name "unconnected-(U3-ADC6-Pad19)") (class "Default")
      (node (ref "U3") (pin "19") (pinfunction "ADC6_19") (pintype "input"))
    )
    (net (code "93") (name "unconnected-(U3-ADC7-Pad22)") (class "Default")
      (node (ref "U3") (pin "22") (pinfunction "ADC7_22") (pintype "input"))
    )
    (net (code "94") (name "unconnected-(U3-AREF-Pad20)") (class "Default")
      (node (ref "U3") (pin "20") (pinfunction "AREF_20") (pintype "passive"))
    )
    (net (code "95") (name "unconnected-(U3-PB0_(PCINT0{slash}CLKO{slash}ICP1)-Pad12)") (class "Default")
      (node (ref "U3") (pin "12") (pinfunction "PB0_(PCINT0/CLKO/ICP1)_12") (pintype "bidirectional"))
    )
    (net (code "96") (name "unconnected-(U3-PB1_(PCINT1{slash}OC1A)-Pad13)") (class "Default")
      (node (ref "U3") (pin "13") (pinfunction "PB1_(PCINT1/OC1A)_13") (pintype "bidirectional"))
    )
    (net (code "97") (name "unconnected-(U3-PC0_(ADC0{slash}PCINT8)-Pad23)") (class "Default")
      (node (ref "U3") (pin "23") (pinfunction "PC0_(ADC0/PCINT8)_23") (pintype "bidirectional"))
    )
    (net (code "98") (name "unconnected-(U3-PC1_(ADC1{slash}PCINT9)-Pad24)") (class "Default")
      (node (ref "U3") (pin "24") (pinfunction "PC1_(ADC1/PCINT9)_24") (pintype "bidirectional"))
    )
    (net (code "99") (name "unconnected-(U3-PC2_(ADC2{slash}PCINT10)-Pad25)") (class "Default")
      (node (ref "U3") (pin "25") (pinfunction "PC2_(ADC2/PCINT10)_25") (pintype "bidirectional"))
    )
    (net (code "100") (name "unconnected-(U3-PD4_(PCINT20{slash}XCK{slash}T0)-Pad2)") (class "Default")
      (node (ref "U3") (pin "2") (pinfunction "PD4_(PCINT20/XCK/T0)_2") (pintype "bidirectional"))
    )
    (net (code "101") (name "unconnected-(U3-PD5_(PCINT21{slash}OC0B{slash}T1)-Pad9)") (class "Default")
      (node (ref "U3") (pin "9") (pinfunction "PD5_(PCINT21/OC0B/T1)_9") (pintype "bidirectional"))
    )
    (net (code "102") (name "unconnected-(U3-PD6_(PCINT22{slash}OC0A{slash}AIN0)-Pad10)") (class "Default")
      (node (ref "U3") (pin "10") (pinfunction "PD6_(PCINT22/OC0A/AIN0)_10") (pintype "bidirectional"))
    )
    (net (code "103") (name "unconnected-(U3-PD7_(PCINT23{slash}AIN1)-Pad11)") (class "Default")
      (node (ref "U3") (pin "11") (pinfunction "PD7_(PCINT23/AIN1)_11") (pintype "bidirectional"))
    )
  )
)
